# BEP31_final.net
KiCad netlist of a schematic drawn in EAGLE
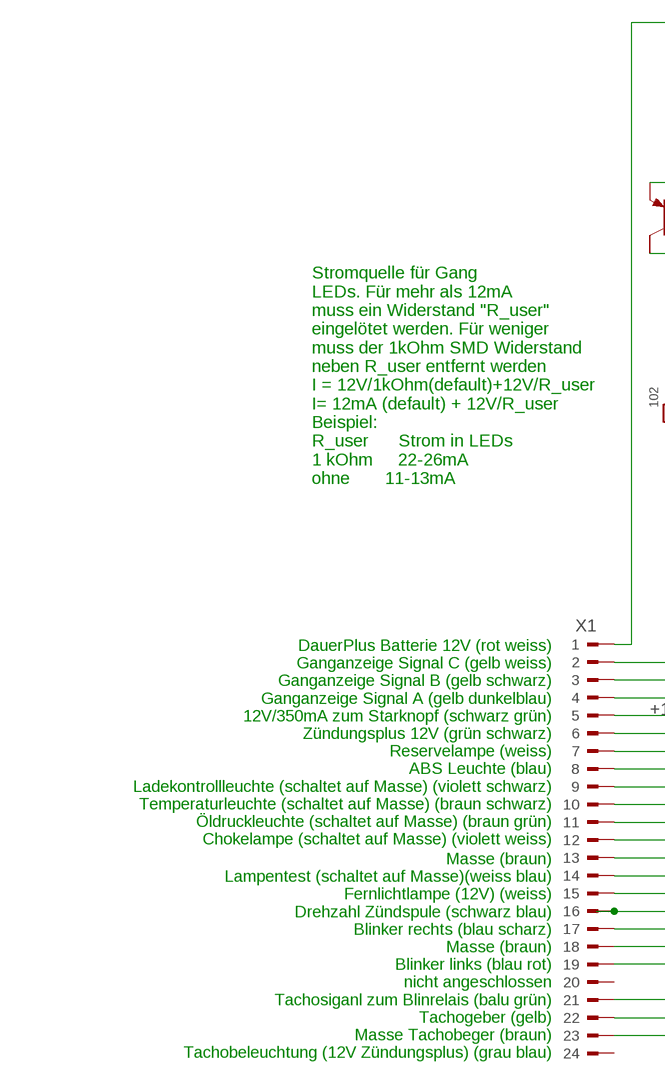
[diagram p0: schematic, sheet 1, part 1 of 2]
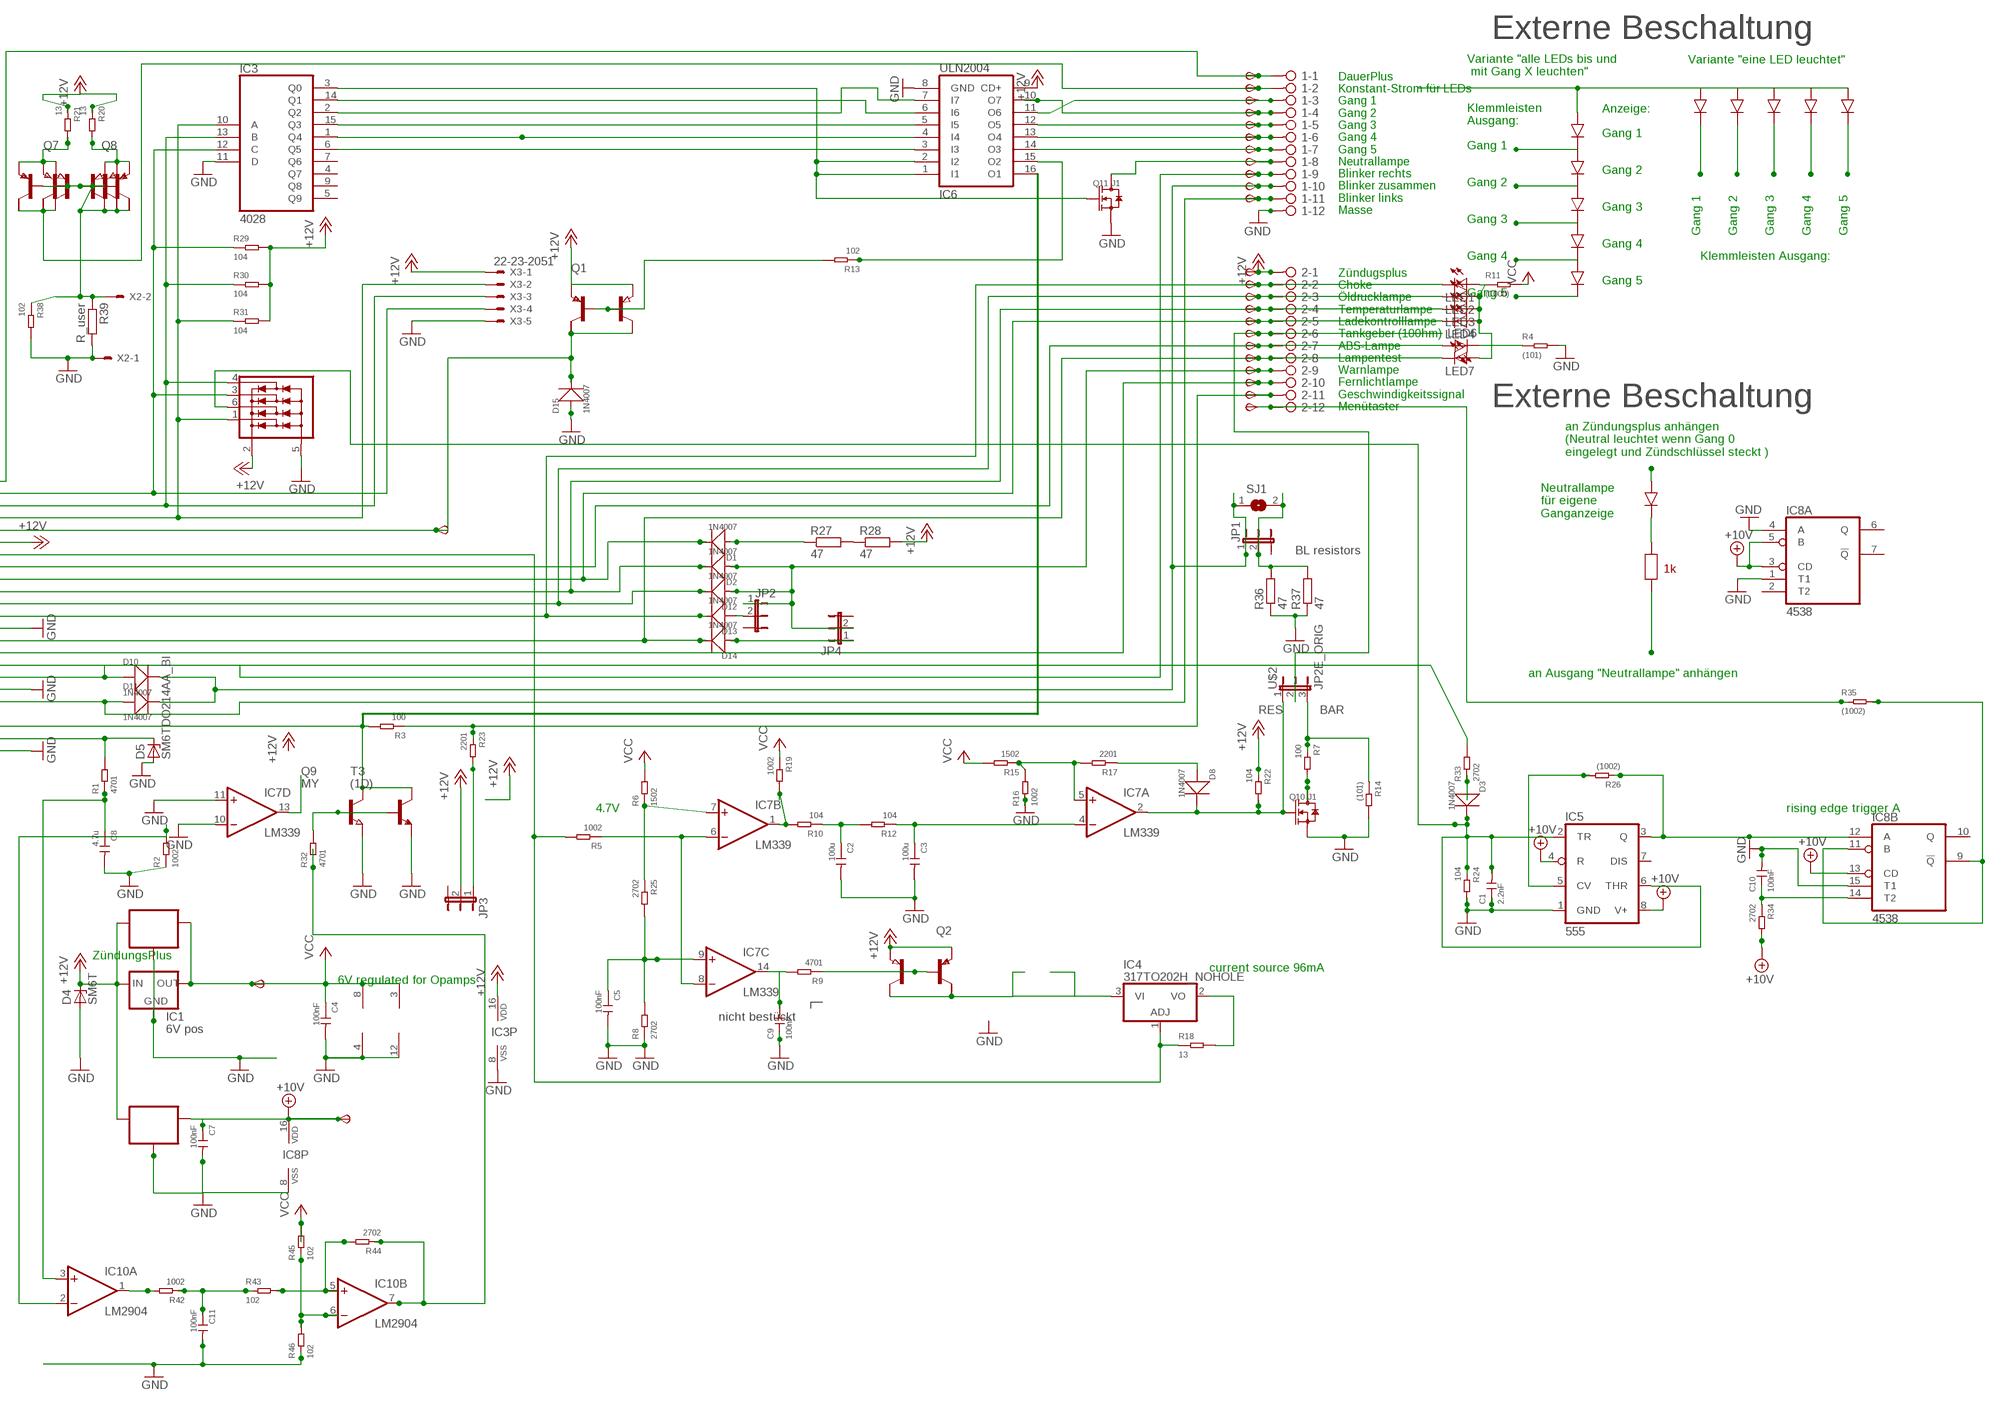
[diagram p1: schematic, sheet 1, part 2 of 2]

(export (version "E")
  (design (tool "Eeschema 10.0.6"))
  (components
    (comp (ref "1")
      (value "2081-1132")
      (footprint "eagle-import:12-PIN")
      (libsource (lib "eagle-import") (part "2081-1132"))
    )
    (comp (ref "2")
      (value "2081-1132")
      (footprint "eagle-import:12-PIN")
      (libsource (lib "eagle-import") (part "2081-1132"))
    )
    (comp (ref "6V")
      (value "TPSB2.0")
      (footprint "eagle-import:B2.0")
      (libsource (lib "eagle-import") (part "TPSB2.0"))
    )
    (comp (ref "10V")
      (value "TPSB2.0")
      (footprint "eagle-import:B2.0")
      (libsource (lib "eagle-import") (part "TPSB2.0"))
    )
    (comp (ref "C1")
      (value "2.2nF")
      (footprint "eagle-import:C0805")
      (fields (field (name "MPN") "CC0805KRX7R9BB104"))
      (libsource (lib "eagle-import") (part "CERAMIC-100NF-50V-10%-X7R(0805)"))
    )
    (comp (ref "C2")
      (value "100u")
      (footprint "eagle-import:C1206")
      (fields (field (name "MPN") "GRM31CR60J107ME39L"))
      (libsource (lib "eagle-import") (part "CERAMIC-100UF-6.3V-20%-X5R(1206)"))
    )
    (comp (ref "C3")
      (value "100u")
      (footprint "eagle-import:C1206")
      (fields (field (name "MPN") "GRM31CR60J107ME39L"))
      (libsource (lib "eagle-import") (part "CERAMIC-100UF-6.3V-20%-X5R(1206)"))
    )
    (comp (ref "C4")
      (value "100nF")
      (footprint "eagle-import:C0805")
      (fields (field (name "MPN") "CC0805KRX7R9BB104"))
      (libsource (lib "eagle-import") (part "CERAMIC-100NF-50V-10%-X7R(0805)"))
    )
    (comp (ref "C5")
      (value "100nF")
      (footprint "eagle-import:C0805")
      (fields (field (name "MPN") "CC0805KRX7R9BB104"))
      (libsource (lib "eagle-import") (part "CERAMIC-100NF-50V-10%-X7R(0805)"))
    )
    (comp (ref "C7")
      (value "100nF")
      (footprint "eagle-import:C0805")
      (fields (field (name "MPN") "CC0805KRX7R9BB104"))
      (libsource (lib "eagle-import") (part "CERAMIC-100NF-50V-10%-X7R(0805)"))
    )
    (comp (ref "C8")
      (value "4.7u")
      (footprint "eagle-import:C0805")
      (fields (field (name "MPN") "CC0805KKX5R8BB475"))
      (libsource (lib "eagle-import") (part "CERAMIC-4.7UF-25V-10%-X5R(0805)"))
    )
    (comp (ref "C9")
      (value "100nF")
      (footprint "eagle-import:C0805")
      (fields (field (name "MPN") "CC0805KRX7R9BB104"))
      (libsource (lib "eagle-import") (part "CERAMIC-100NF-50V-10%-X7R(0805)"))
    )
    (comp (ref "C10")
      (value "100nF")
      (footprint "eagle-import:C0805")
      (fields (field (name "MPN") "CC0805KRX7R9BB104"))
      (libsource (lib "eagle-import") (part "CERAMIC-100NF-50V-10%-X7R(0805)"))
    )
    (comp (ref "C11")
      (value "100nF")
      (footprint "eagle-import:C0805")
      (fields (field (name "MPN") "CC0805KRX7R9BB104"))
      (libsource (lib "eagle-import") (part "CERAMIC-100NF-50V-10%-X7R(0805)"))
    )
    (comp (ref "D1")
      (value "1N4007")
      (footprint "eagle-import:DO-214AC")
      (libsource (lib "eagle-import") (part "DIODE-GEN-PURPOSE-1KV-1A(DO-214AC)"))
    )
    (comp (ref "D2")
      (value "1N4007")
      (footprint "eagle-import:DO-214AC-1206MOUNT")
      (libsource (lib "eagle-import") (part "DIODE-GEN-PURPOSE-1KV-1A(DO-214AC)DO-214AC/1206"))
    )
    (comp (ref "D3")
      (value "1N4007")
      (footprint "eagle-import:DO-214AC")
      (libsource (lib "eagle-import") (part "DIODE-GEN-PURPOSE-1KV-1A(DO-214AC)"))
    )
    (comp (ref "D4")
      (value "SM6T")
      (footprint "eagle-import:DO214AA")
      (libsource (lib "eagle-import") (part "SM6T"))
    )
    (comp (ref "D5")
      (value "SM6TDO214AA_BI")
      (footprint "eagle-import:DO214AA_BI")
      (libsource (lib "eagle-import") (part "SM6TDO214AA_BI"))
    )
    (comp (ref "D8")
      (value "1N4007")
      (footprint "eagle-import:DO-214AC")
      (libsource (lib "eagle-import") (part "DIODE-GEN-PURPOSE-1KV-1A(DO-214AC)"))
    )
    (comp (ref "D10")
      (value "1N4007")
      (footprint "eagle-import:DO-214AC")
      (libsource (lib "eagle-import") (part "DIODE-GEN-PURPOSE-1KV-1A(DO-214AC)"))
    )
    (comp (ref "D11")
      (value "1N4007")
      (footprint "eagle-import:DO-214AC")
      (libsource (lib "eagle-import") (part "DIODE-GEN-PURPOSE-1KV-1A(DO-214AC)"))
    )
    (comp (ref "D12")
      (value "1N4007")
      (footprint "eagle-import:DO-214AC-1206MOUNT")
      (libsource (lib "eagle-import") (part "DIODE-GEN-PURPOSE-1KV-1A(DO-214AC)DO-214AC/1206"))
    )
    (comp (ref "D13")
      (value "1N4007")
      (footprint "eagle-import:DO-214AC-1206MOUNT")
      (libsource (lib "eagle-import") (part "DIODE-GEN-PURPOSE-1KV-1A(DO-214AC)DO-214AC/1206"))
    )
    (comp (ref "D14")
      (value "1N4007")
      (footprint "eagle-import:DO-214AC-1206MOUNT")
      (libsource (lib "eagle-import") (part "DIODE-GEN-PURPOSE-1KV-1A(DO-214AC)DO-214AC/1206"))
    )
    (comp (ref "D15")
      (value "1N4007")
      (footprint "eagle-import:DO-214AC")
      (libsource (lib "eagle-import") (part "DIODE-GEN-PURPOSE-1KV-1A(DO-214AC)"))
    )
    (comp (ref "IC1")
      (value "6V pos")
      (footprint "eagle-import:78LXX")
      (libsource (lib "eagle-import") (part "v-reg_78LXX"))
    )
    (comp (ref "IC2")
      (value "78LXXSOT89_ROUND")
      (footprint "eagle-import:SOT89_ROUND")
      (libsource (lib "eagle-import") (part "78LXXSOT89_ROUND"))
    )
    (comp (ref "IC3")
      (value "4028")
      (footprint "eagle-import:SO16")
      (libsource (lib "eagle-import") (part "4028D"))
    )
    (comp (ref "IC4")
      (value "317TO202H_NOHOLE")
      (footprint "eagle-import:TO220H_NOHOLE")
      (libsource (lib "eagle-import") (part "317TO202H_NOHOLE"))
    )
    (comp (ref "IC5")
      (value "555")
      (footprint "eagle-import:SO08")
      (libsource (lib "eagle-import") (part "555DNE"))
    )
    (comp (ref "IC6")
      (value "ULN2004")
      (footprint "eagle-import:SO16")
      (libsource (lib "eagle-import") (part "ULN2004AD"))
    )
    (comp (ref "IC7")
      (value "LM339")
      (footprint "eagle-import:SO14")
      (libsource (lib "eagle-import") (part "LM339D"))
    )
    (comp (ref "IC8")
      (value "4538")
      (footprint "eagle-import:SO16")
      (libsource (lib "eagle-import") (part "4538D"))
    )
    (comp (ref "IC9")
      (value "78LXXSOT89_ROUND")
      (footprint "eagle-import:SOT89_ROUND")
      (libsource (lib "eagle-import") (part "78LXXSOT89_ROUND"))
    )
    (comp (ref "IC10")
      (value "LM2904")
      (footprint "eagle-import:SO08")
      (libsource (lib "eagle-import") (part "LM358D"))
    )
    (comp (ref "JP1")
      (value "JP2EJP2_SMALLPADS")
      (footprint "eagle-import:JP2_SMALLPADS")
      (libsource (lib "eagle-import") (part "JP2EJP2_SMALLPADS"))
    )
    (comp (ref "JP2")
      (value "JP2EJP2_SMALLPADS")
      (footprint "eagle-import:JP2_SMALLPADS")
      (libsource (lib "eagle-import") (part "JP2EJP2_SMALLPADS"))
    )
    (comp (ref "JP3")
      (value "JP2EJP2_SMALLPADS")
      (footprint "eagle-import:JP2_SMALLPADS")
      (libsource (lib "eagle-import") (part "JP2EJP2_SMALLPADS"))
    )
    (comp (ref "JP4")
      (value "JP2EJP2_SMALLPADS")
      (footprint "eagle-import:JP2_SMALLPADS")
      (libsource (lib "eagle-import") (part "JP2EJP2_SMALLPADS"))
    )
    (comp (ref "LED1")
      (value "LEDLD260")
      (footprint "eagle-import:LD260")
      (libsource (lib "eagle-import") (part "LEDLD260"))
    )
    (comp (ref "LED2")
      (value "LEDLD260")
      (footprint "eagle-import:LD260")
      (libsource (lib "eagle-import") (part "LEDLD260"))
    )
    (comp (ref "LED3")
      (value "LEDLD260")
      (footprint "eagle-import:LD260")
      (libsource (lib "eagle-import") (part "LEDLD260"))
    )
    (comp (ref "LED4")
      (value "LEDLD260")
      (footprint "eagle-import:LD260")
      (libsource (lib "eagle-import") (part "LEDLD260"))
    )
    (comp (ref "LED6")
      (value "LEDLD260")
      (footprint "eagle-import:LD260")
      (libsource (lib "eagle-import") (part "LEDLD260"))
    )
    (comp (ref "LED7")
      (value "LEDLD260")
      (footprint "eagle-import:LD260")
      (libsource (lib "eagle-import") (part "LEDLD260"))
    )
    (comp (ref "Q1")
      (value "PNP-TRANSISTOR_SOT89")
      (footprint "eagle-import:SOT89")
      (libsource (lib "eagle-import") (part "PNP-TRANSISTOR_SOT89"))
    )
    (comp (ref "Q2")
      (value "PNP-TRANSISTOR_SOT89")
      (footprint "eagle-import:SOT89")
      (libsource (lib "eagle-import") (part "PNP-TRANSISTOR_SOT89"))
    )
    (comp (ref "Q3")
      (value "AH-16")
      (footprint "eagle-import:SOT223")
      (libsource (lib "eagle-import") (part "BCP53T1"))
    )
    (comp (ref "Q4")
      (value "(AH-16)")
      (footprint "eagle-import:SOT223")
      (libsource (lib "eagle-import") (part "BCP53T1"))
    )
    (comp (ref "Q5")
      (value "(AH-16)")
      (footprint "eagle-import:SOT223")
      (libsource (lib "eagle-import") (part "BCP53T1"))
    )
    (comp (ref "Q6")
      (value "(AH-16)")
      (footprint "eagle-import:SOT223")
      (libsource (lib "eagle-import") (part "BCP53T1"))
    )
    (comp (ref "Q7")
      (value "PNP-TRANSISTOR_SOT89")
      (footprint "eagle-import:SOT89")
      (libsource (lib "eagle-import") (part "PNP-TRANSISTOR_SOT89"))
    )
    (comp (ref "Q8")
      (value "PNP-TRANSISTOR_SOT89")
      (footprint "eagle-import:SOT89")
      (libsource (lib "eagle-import") (part "PNP-TRANSISTOR_SOT89"))
    )
    (comp (ref "Q9")
      (value "MY")
      (footprint "eagle-import:SOT89")
      (libsource (lib "eagle-import") (part "NPN-TRANSISTOR_SOT89"))
    )
    (comp (ref "Q10")
      (value "J1")
      (footprint "eagle-import:SOT-23")
      (fields (field (name "MPN") "BSS138W-7-F"))
      (libsource (lib "eagle-import") (part "SMD-MOSFET-N-CH-50V-200MA-BSS138W-7-F(SOT-23)"))
    )
    (comp (ref "Q11")
      (value "J1")
      (footprint "eagle-import:SOT-23")
      (fields (field (name "MPN") "BSS138W-7-F"))
      (libsource (lib "eagle-import") (part "SMD-MOSFET-N-CH-50V-200MA-BSS138W-7-F(SOT-23)"))
    )
    (comp (ref "R1")
      (value "4701")
      (footprint "eagle-import:R0805")
      (fields (field (name "MPN") "RC0805JR-074K7L"))
      (libsource (lib "eagle-import") (part "SMD-RES-4.7K-5%-1/8W(0805)"))
    )
    (comp (ref "R2")
      (value "1002")
      (footprint "eagle-import:R0805")
      (fields (field (name "MPN") "RC0805FR-0710KL"))
      (libsource (lib "eagle-import") (part "SMD-RES-10K-1%-1/8W(0805)"))
    )
    (comp (ref "R3")
      (value "100")
      (footprint "eagle-import:R0805")
      (fields (field (name "MPN") "RC0805JR-07220RL"))
      (libsource (lib "eagle-import") (part "SMD-RES-220R-5%-1/8W(0805)"))
    )
    (comp (ref "R4")
      (value "(101)")
      (footprint "eagle-import:R0805")
      (fields (field (name "MPN") "RC0805JR-07100RL"))
      (libsource (lib "eagle-import") (part "SMD-RES-100R-5%-1/8W(0805)"))
    )
    (comp (ref "R5")
      (value "1002")
      (footprint "eagle-import:R0805")
      (fields (field (name "MPN") "RC0805FR-0710KL"))
      (libsource (lib "eagle-import") (part "SMD-RES-10K-1%-1/8W(0805)"))
    )
    (comp (ref "R6")
      (value "1502")
      (footprint "eagle-import:R0805")
      (fields (field (name "MPN") "RC0805FR-0710KL"))
      (libsource (lib "eagle-import") (part "SMD-RES-10K-1%-1/8W(0805)"))
    )
    (comp (ref "R7")
      (value "100")
      (footprint "eagle-import:R0805")
      (fields (field (name "MPN") "RC0805JR-072K2L"))
      (libsource (lib "eagle-import") (part "SMD-RES-2.2K-5%-1/8W(0805)"))
    )
    (comp (ref "R8")
      (value "2702")
      (footprint "eagle-import:R0805")
      (fields (field (name "MPN") "RC0805JR-074K7L"))
      (libsource (lib "eagle-import") (part "SMD-RES-4.7K-5%-1/8W(0805)"))
    )
    (comp (ref "R9")
      (value "4701")
      (footprint "eagle-import:R0805")
      (fields (field (name "MPN") "RC0805JR-074K7L"))
      (libsource (lib "eagle-import") (part "SMD-RES-4.7K-5%-1/8W(0805)"))
    )
    (comp (ref "R10")
      (value "104")
      (footprint "eagle-import:R0805")
      (fields (field (name "MPN") "RC0805FR-0710KL"))
      (libsource (lib "eagle-import") (part "SMD-RES-10K-1%-1/8W(0805)"))
    )
    (comp (ref "R11")
      (value "(1000)")
      (footprint "eagle-import:R0805")
      (fields (field (name "MPN") "RC0805JR-07100RL"))
      (libsource (lib "eagle-import") (part "SMD-RES-100R-5%-1/8W(0805)"))
    )
    (comp (ref "R12")
      (value "104")
      (footprint "eagle-import:R0805")
      (fields (field (name "MPN") "RC0805FR-0710KL"))
      (libsource (lib "eagle-import") (part "SMD-RES-10K-1%-1/8W(0805)"))
    )
    (comp (ref "R13")
      (value "102")
      (footprint "eagle-import:R0805")
      (fields (field (name "MPN") "RC0805JR-071KL"))
      (libsource (lib "eagle-import") (part "SMD-RES-1K-5%-1/8W(0805)"))
    )
    (comp (ref "R14")
      (value "(101)")
      (footprint "eagle-import:R0805")
      (fields (field (name "MPN") "RC0805JR-072K2L"))
      (libsource (lib "eagle-import") (part "SMD-RES-2.2K-5%-1/8W(0805)"))
    )
    (comp (ref "R15")
      (value "1502")
      (footprint "eagle-import:R0805")
      (fields (field (name "MPN") "RC0805FR-0710KL"))
      (libsource (lib "eagle-import") (part "SMD-RES-10K-1%-1/8W(0805)"))
    )
    (comp (ref "R16")
      (value "1002")
      (footprint "eagle-import:R0805")
      (fields (field (name "MPN") "RC0805FR-0710KL"))
      (libsource (lib "eagle-import") (part "SMD-RES-10K-1%-1/8W(0805)"))
    )
    (comp (ref "R17")
      (value "2201")
      (footprint "eagle-import:R0805")
      (fields (field (name "MPN") "RC0805JR-072K2L"))
      (libsource (lib "eagle-import") (part "SMD-RES-2.2K-5%-1/8W(0805)"))
    )
    (comp (ref "R18")
      (value "13")
      (footprint "eagle-import:R1206")
      (fields (field (name "MPN") "RC1206JR-0713RL"))
      (libsource (lib "eagle-import") (part "SMD-RES-13R-5%-1/4W(1206)"))
    )
    (comp (ref "R19")
      (value "1002")
      (footprint "eagle-import:R0805")
      (fields (field (name "MPN") "RC0805FR-0710KL"))
      (libsource (lib "eagle-import") (part "SMD-RES-10K-1%-1/8W(0805)"))
    )
    (comp (ref "R20")
      (value "13")
      (footprint "eagle-import:R1206")
      (fields (field (name "MPN") "RC1206JR-0713RL"))
      (libsource (lib "eagle-import") (part "SMD-RES-13R-5%-1/4W(1206)"))
    )
    (comp (ref "R21")
      (value "13")
      (footprint "eagle-import:R1206")
      (fields (field (name "MPN") "RC1206JR-0713RL"))
      (libsource (lib "eagle-import") (part "SMD-RES-13R-5%-1/4W(1206)"))
    )
    (comp (ref "R22")
      (value "104")
      (footprint "eagle-import:R0805")
      (fields (field (name "MPN") "RC0805FR-0710KL"))
      (libsource (lib "eagle-import") (part "SMD-RES-10K-1%-1/8W(0805)"))
    )
    (comp (ref "R23")
      (value "2201")
      (footprint "eagle-import:R0805")
      (fields (field (name "MPN") "RC0805JR-072K2L"))
      (libsource (lib "eagle-import") (part "SMD-RES-2.2K-5%-1/8W(0805)"))
    )
    (comp (ref "R24")
      (value "104")
      (footprint "eagle-import:R0805")
      (fields (field (name "MPN") "RC0805FR-0710KL"))
      (libsource (lib "eagle-import") (part "SMD-RES-10K-1%-1/8W(0805)"))
    )
    (comp (ref "R25")
      (value "2702")
      (footprint "eagle-import:R0805")
      (fields (field (name "MPN") "RC0805JR-074K7L"))
      (libsource (lib "eagle-import") (part "SMD-RES-4.7K-5%-1/8W(0805)"))
    )
    (comp (ref "R26")
      (value "(1002)")
      (footprint "eagle-import:R0805")
      (fields (field (name "MPN") "RC0805FR-0710KL"))
      (libsource (lib "eagle-import") (part "SMD-RES-10K-1%-1/8W(0805)"))
    )
    (comp (ref "R27")
      (value "47")
      (footprint "eagle-import:V235_17_1MM")
      (libsource (lib "eagle-import") (part "R-EU_V235/17_1MM"))
    )
    (comp (ref "R28")
      (value "47")
      (footprint "eagle-import:V235_17_1MM")
      (libsource (lib "eagle-import") (part "R-EU_V235/17_1MM"))
    )
    (comp (ref "R29")
      (value "104")
      (footprint "eagle-import:R0805")
      (fields (field (name "MPN") "RC0805FR-0710KL"))
      (libsource (lib "eagle-import") (part "SMD-RES-10K-1%-1/8W(0805)"))
    )
    (comp (ref "R30")
      (value "104")
      (footprint "eagle-import:R0805")
      (fields (field (name "MPN") "RC0805FR-0710KL"))
      (libsource (lib "eagle-import") (part "SMD-RES-10K-1%-1/8W(0805)"))
    )
    (comp (ref "R31")
      (value "104")
      (footprint "eagle-import:R0805")
      (fields (field (name "MPN") "RC0805FR-0710KL"))
      (libsource (lib "eagle-import") (part "SMD-RES-10K-1%-1/8W(0805)"))
    )
    (comp (ref "R32")
      (value "4701")
      (footprint "eagle-import:R0805")
      (fields (field (name "MPN") "RC0805JR-074K7L"))
      (libsource (lib "eagle-import") (part "SMD-RES-4.7K-5%-1/8W(0805)"))
    )
    (comp (ref "R33")
      (value "2702")
      (footprint "eagle-import:R0805")
      (fields (field (name "MPN") "RC0805FR-0710KL"))
      (libsource (lib "eagle-import") (part "SMD-RES-10K-1%-1/8W(0805)"))
    )
    (comp (ref "R34")
      (value "2702")
      (footprint "eagle-import:R0805")
      (fields (field (name "MPN") "RC0805JR-074K7L"))
      (libsource (lib "eagle-import") (part "SMD-RES-4.7K-5%-1/8W(0805)"))
    )
    (comp (ref "R35")
      (value "(1002)")
      (footprint "eagle-import:R0805")
      (fields (field (name "MPN") "RC0805JR-074K7L"))
      (libsource (lib "eagle-import") (part "SMD-RES-4.7K-5%-1/8W(0805)"))
    )
    (comp (ref "R36")
      (value "47")
      (footprint "eagle-import:V235_17_1MM")
      (libsource (lib "eagle-import") (part "R-EU_V235/17_1MM"))
    )
    (comp (ref "R37")
      (value "47")
      (footprint "eagle-import:V235_17_1MM")
      (libsource (lib "eagle-import") (part "R-EU_V235/17_1MM"))
    )
    (comp (ref "R38")
      (value "102")
      (footprint "eagle-import:R0805")
      (fields (field (name "MPN") "RC0805JR-071KL"))
      (libsource (lib "eagle-import") (part "SMD-RES-1K-5%-1/8W(0805)"))
    )
    (comp (ref "R39")
      (value "R_user")
      (footprint "eagle-import:R0805")
      (libsource (lib "eagle-import") (part "R-EU_R0805"))
    )
    (comp (ref "R42")
      (value "1002")
      (footprint "eagle-import:R0805")
      (fields (field (name "MPN") "RC0805FR-0710KL"))
      (libsource (lib "eagle-import") (part "SMD-RES-10K-1%-1/8W(0805)"))
    )
    (comp (ref "R43")
      (value "102")
      (footprint "eagle-import:R0805")
      (fields (field (name "MPN") "RC0805JR-071KL"))
      (libsource (lib "eagle-import") (part "SMD-RES-1K-5%-1/8W(0805)"))
    )
    (comp (ref "R44")
      (value "2702")
      (footprint "eagle-import:R0805")
      (fields (field (name "MPN") "RC0805JR-074K7L"))
      (libsource (lib "eagle-import") (part "SMD-RES-4.7K-5%-1/8W(0805)"))
    )
    (comp (ref "R45")
      (value "102")
      (footprint "eagle-import:R0805")
      (fields (field (name "MPN") "RC0805JR-071KL"))
      (libsource (lib "eagle-import") (part "SMD-RES-1K-5%-1/8W(0805)"))
    )
    (comp (ref "R46")
      (value "102")
      (footprint "eagle-import:R0805")
      (fields (field (name "MPN") "RC0805JR-071KL"))
      (libsource (lib "eagle-import") (part "SMD-RES-1K-5%-1/8W(0805)"))
    )
    (comp (ref "SJ1") (value "SJ") (footprint "eagle-import:SJ") (libsource (lib "eagle-import") (part "SJ")))
    (comp (ref "START")
      (value "TPSB2.0")
      (footprint "eagle-import:B2.0")
      (libsource (lib "eagle-import") (part "TPSB2.0"))
    )
    (comp (ref "T1")
      (value "PNP2SM8")
      (footprint "eagle-import:SM8")
      (libsource (lib "eagle-import") (part "PNP2SM8"))
    )
    (comp (ref "T3")
      (value "(1D)")
      (footprint "eagle-import:SOT23-BEC")
      (libsource (lib "eagle-import") (part "-NPN-SOT23-BECMMBTA42LT1"))
    )
    (comp (ref "TP1")
      (value "TPSB2.0")
      (footprint "eagle-import:B2.0")
      (libsource (lib "eagle-import") (part "TPSB2.0"))
    )
    (comp (ref "TP2")
      (value "TPSB2.0")
      (footprint "eagle-import:B2.0")
      (libsource (lib "eagle-import") (part "TPSB2.0"))
    )
    (comp (ref "TP3")
      (value "TPSB2.0")
      (footprint "eagle-import:B2.0")
      (libsource (lib "eagle-import") (part "TPSB2.0"))
    )
    (comp (ref "TP4")
      (value "TPSB2.0")
      (footprint "eagle-import:B2.0")
      (libsource (lib "eagle-import") (part "TPSB2.0"))
    )
    (comp (ref "TP5")
      (value "TPSB2.0")
      (footprint "eagle-import:B2.0")
      (libsource (lib "eagle-import") (part "TPSB2.0"))
    )
    (comp (ref "TP6")
      (value "TPSB2.0")
      (footprint "eagle-import:B2.0")
      (libsource (lib "eagle-import") (part "TPSB2.0"))
    )
    (comp (ref "TP7")
      (value "TPSB2.0")
      (footprint "eagle-import:B2.0")
      (libsource (lib "eagle-import") (part "TPSB2.0"))
    )
    (comp (ref "TP8")
      (value "TPSB2.0")
      (footprint "eagle-import:B2.0")
      (libsource (lib "eagle-import") (part "TPSB2.0"))
    )
    (comp (ref "TP9")
      (value "TPSB2.0")
      (footprint "eagle-import:B2.0")
      (libsource (lib "eagle-import") (part "TPSB2.0"))
    )
    (comp (ref "TP10")
      (value "TPSB2.0")
      (footprint "eagle-import:B2.0")
      (libsource (lib "eagle-import") (part "TPSB2.0"))
    )
    (comp (ref "TP11")
      (value "TPSB2.0")
      (footprint "eagle-import:B2.0")
      (libsource (lib "eagle-import") (part "TPSB2.0"))
    )
    (comp (ref "TP12")
      (value "TPSB2.0")
      (footprint "eagle-import:B2.0")
      (libsource (lib "eagle-import") (part "TPSB2.0"))
    )
    (comp (ref "TP13")
      (value "TPSB2.0")
      (footprint "eagle-import:B2.0")
      (libsource (lib "eagle-import") (part "TPSB2.0"))
    )
    (comp (ref "TP16")
      (value "TPSB2.0")
      (footprint "eagle-import:B2.0")
      (libsource (lib "eagle-import") (part "TPSB2.0"))
    )
    (comp (ref "TP17")
      (value "TPSB2.0")
      (footprint "eagle-import:B2.0")
      (libsource (lib "eagle-import") (part "TPSB2.0"))
    )
    (comp (ref "TP18")
      (value "TPSB2.0")
      (footprint "eagle-import:B2.0")
      (libsource (lib "eagle-import") (part "TPSB2.0"))
    )
    (comp (ref "TP19")
      (value "TPSB2.0")
      (footprint "eagle-import:B2.0")
      (libsource (lib "eagle-import") (part "TPSB2.0"))
    )
    (comp (ref "TP21")
      (value "TPSB2.0")
      (footprint "eagle-import:B2.0")
      (libsource (lib "eagle-import") (part "TPSB2.0"))
    )
    (comp (ref "TP22")
      (value "TPSB2.0")
      (footprint "eagle-import:B2.0")
      (libsource (lib "eagle-import") (part "TPSB2.0"))
    )
    (comp (ref "TP23")
      (value "TPSB2.0")
      (footprint "eagle-import:B2.0")
      (libsource (lib "eagle-import") (part "TPSB2.0"))
    )
    (comp (ref "TP24")
      (value "TPSB1,27")
      (footprint "eagle-import:B1,27")
      (libsource (lib "eagle-import") (part "TPSB1,27"))
    )
    (comp (ref "TP25")
      (value "TPSB2.0")
      (footprint "eagle-import:B2.0")
      (libsource (lib "eagle-import") (part "TPSB2.0"))
    )
    (comp (ref "TP26")
      (value "TPSB2.0")
      (footprint "eagle-import:B2.0")
      (libsource (lib "eagle-import") (part "TPSB2.0"))
    )
    (comp (ref "U$2")
      (value "JP2E_ORIG")
      (footprint "eagle-import:JP2_ORIG_SMALLPADS")
      (libsource (lib "eagle-import") (part "JP2E_ORIG"))
    )
    (comp (ref "U$3")
      (value "NUP4304SOT457_R")
      (footprint "eagle-import:SOT457R_PHILIPS")
      (libsource (lib "eagle-import") (part "NUP4304SOT457_R"))
    )
    (comp (ref "X1")
      (value "CON_BMWV2")
      (footprint "eagle-import:24-PIN_V2")
      (libsource (lib "eagle-import") (part "CON_BMWV2"))
    )
    (comp (ref "X2")
      (value "22-23-2021")
      (footprint "eagle-import:22-23-2021")
      (fields (field (name "MF") "MOLEX"))
      (libsource (lib "eagle-import") (part "22-23-2021"))
    )
    (comp (ref "X3")
      (value "22-23-2051")
      (footprint "eagle-import:22-23-2051")
      (fields (field (name "MF") "MOLEX"))
      (libsource (lib "eagle-import") (part "22-23-2051"))
    )
  )
  (nets
    (net (code "1") (name "+10V") (class "Default")
      (node (ref "10V") (pin "TP") (pinfunction "PP_TP") (pintype "input"))
      (node (ref "C7") (pin "1") (pinfunction "1_1") (pintype "passive"))
      (node (ref "IC5") (pin "4") (pinfunction "R_4") (pintype "input"))
      (node (ref "IC5") (pin "8") (pinfunction "V+_8") (pintype "power_in"))
      (node (ref "IC8") (pin "13") (pinfunction "CD_13") (pintype "input"))
      (node (ref "IC8") (pin "16") (pinfunction "VDD_16") (pintype "power_in"))
      (node (ref "IC8") (pin "3") (pinfunction "CD_3") (pintype "input"))
      (node (ref "IC8") (pin "5") (pinfunction "B_5") (pintype "input"))
      (node (ref "IC9") (pin "1") (pinfunction "OUT_1") (pintype "passive"))
      (node (ref "R34") (pin "2") (pinfunction "2_2") (pintype "passive"))
    )
    (net (code "2") (name "+12V") (class "Default")
      (node (ref "2") (pin "1") (pinfunction "KL_1") (pintype "passive"))
      (node (ref "D4") (pin "C") (pinfunction "C_C") (pintype "passive"))
      (node (ref "IC1") (pin "IN") (pinfunction "IN_IN") (pintype "input"))
      (node (ref "IC2") (pin "3") (pinfunction "IN_3") (pintype "input"))
      (node (ref "IC3") (pin "16") (pinfunction "VDD_16") (pintype "power_in"))
      (node (ref "IC6") (pin "9") (pinfunction "CD+_9") (pintype "passive"))
      (node (ref "IC9") (pin "3") (pinfunction "IN_3") (pintype "input"))
      (node (ref "JP3") (pin "2") (pinfunction "2_2") (pintype "passive"))
      (node (ref "Q1") (pin "3") (pinfunction "E_3") (pintype "passive"))
      (node (ref "Q2") (pin "3") (pinfunction "E_3") (pintype "passive"))
      (node (ref "Q3") (pin "3") (pinfunction "E_3") (pintype "passive"))
      (node (ref "Q4") (pin "3") (pinfunction "E_3") (pintype "passive"))
      (node (ref "R20") (pin "1") (pinfunction "1_1") (pintype "passive"))
      (node (ref "R21") (pin "1") (pinfunction "1_1") (pintype "passive"))
      (node (ref "R22") (pin "1") (pinfunction "1_1") (pintype "passive"))
      (node (ref "R28") (pin "2") (pinfunction "2_2") (pintype "passive"))
      (node (ref "R29") (pin "2") (pinfunction "2_2") (pintype "passive"))
      (node (ref "R30") (pin "2") (pinfunction "2_2") (pintype "passive"))
      (node (ref "R31") (pin "2") (pinfunction "2_2") (pintype "passive"))
      (node (ref "TP12") (pin "TP") (pinfunction "PP_TP") (pintype "input"))
      (node (ref "U$3") (pin "2") (pinfunction "V+_2") (pintype "passive"))
      (node (ref "X1") (pin "6") (pinfunction "6_6") (pintype "passive"))
      (node (ref "X3") (pin "1") (pinfunction "S_1") (pintype "passive"))
    )
    (net (code "3") (name "GND") (class "Default")
      (node (ref "1") (pin "12") (pinfunction "KL_12") (pintype "passive"))
      (node (ref "C1") (pin "1") (pinfunction "1_1") (pintype "passive"))
      (node (ref "C10") (pin "2") (pinfunction "2_2") (pintype "passive"))
      (node (ref "C11") (pin "2") (pinfunction "2_2") (pintype "passive"))
      (node (ref "C2") (pin "2") (pinfunction "2_2") (pintype "passive"))
      (node (ref "C3") (pin "2") (pinfunction "2_2") (pintype "passive"))
      (node (ref "C4") (pin "2") (pinfunction "2_2") (pintype "passive"))
      (node (ref "C5") (pin "2") (pinfunction "2_2") (pintype "passive"))
      (node (ref "C7") (pin "2") (pinfunction "2_2") (pintype "passive"))
      (node (ref "C8") (pin "2") (pinfunction "2_2") (pintype "passive"))
      (node (ref "C9") (pin "1") (pinfunction "1_1") (pintype "passive"))
      (node (ref "D15") (pin "1") (pinfunction "+_1") (pintype "passive"))
      (node (ref "D4") (pin "A") (pinfunction "A_A") (pintype "passive"))
      (node (ref "D5") (pin "A") (pinfunction "A_A") (pintype "passive"))
      (node (ref "IC1") (pin "GND") (pinfunction "GND_GND") (pintype "input"))
      (node (ref "IC10") (pin "4") (pinfunction "V-_4") (pintype "power_in"))
      (node (ref "IC2") (pin "2") (pinfunction "GND_2") (pintype "input"))
      (node (ref "IC2") (pin "2@1") (pinfunction "GND_2@1") (pintype "input"))
      (node (ref "IC3") (pin "11") (pinfunction "D_11") (pintype "input"))
      (node (ref "IC3") (pin "8") (pinfunction "VSS_8") (pintype "power_in"))
      (node (ref "IC5") (pin "1") (pinfunction "GND_1") (pintype "power_in"))
      (node (ref "IC6") (pin "8") (pinfunction "GND_8") (pintype "power_in"))
      (node (ref "IC7") (pin "10") (pinfunction "-IN_10") (pintype "input"))
      (node (ref "IC7") (pin "11") (pinfunction "+IN_11") (pintype "input"))
      (node (ref "IC7") (pin "12") (pinfunction "GND_12") (pintype "power_in"))
      (node (ref "IC8") (pin "1") (pinfunction "T1_1") (pintype "input"))
      (node (ref "IC8") (pin "15") (pinfunction "T1_15") (pintype "input"))
      (node (ref "IC8") (pin "4") (pinfunction "A_4") (pintype "input"))
      (node (ref "IC8") (pin "8") (pinfunction "VSS_8") (pintype "power_in"))
      (node (ref "IC9") (pin "2") (pinfunction "GND_2") (pintype "input"))
      (node (ref "IC9") (pin "2@1") (pinfunction "GND_2@1") (pintype "input"))
      (node (ref "Q10") (pin "2") (pinfunction "S_2") (pintype "passive"))
      (node (ref "Q11") (pin "2") (pinfunction "S_2") (pintype "passive"))
      (node (ref "Q9") (pin "3") (pinfunction "E_3") (pintype "passive"))
      (node (ref "R14") (pin "2") (pinfunction "2_2") (pintype "passive"))
      (node (ref "R16") (pin "1") (pinfunction "1_1") (pintype "passive"))
      (node (ref "R2") (pin "1") (pinfunction "1_1") (pintype "passive"))
      (node (ref "R24") (pin "2") (pinfunction "2_2") (pintype "passive"))
      (node (ref "R36") (pin "1") (pinfunction "1_1") (pintype "passive"))
      (node (ref "R37") (pin "1") (pinfunction "1_1") (pintype "passive"))
      (node (ref "R38") (pin "2") (pinfunction "2_2") (pintype "passive"))
      (node (ref "R39") (pin "2") (pinfunction "2_2") (pintype "passive"))
      (node (ref "R4") (pin "2") (pinfunction "2_2") (pintype "passive"))
      (node (ref "R46") (pin "1") (pinfunction "1_1") (pintype "passive"))
      (node (ref "R8") (pin "1") (pinfunction "1_1") (pintype "passive"))
      (node (ref "T3") (pin "E") (pinfunction "E_E") (pintype "passive"))
      (node (ref "U$3") (pin "5") (pinfunction "V-_5") (pintype "passive"))
      (node (ref "X1") (pin "13") (pinfunction "13_13") (pintype "passive"))
      (node (ref "X1") (pin "18") (pinfunction "18_18") (pintype "passive"))
      (node (ref "X1") (pin "23") (pinfunction "23_23") (pintype "passive"))
      (node (ref "X2") (pin "1") (pinfunction "S_1") (pintype "passive"))
      (node (ref "X3") (pin "5") (pinfunction "S_5") (pintype "passive"))
    )
    (net (code "4") (name "Net-(1A-KL)") (class "Default")
      (node (ref "1") (pin "1") (pinfunction "KL_1") (pintype "passive"))
      (node (ref "TP1") (pin "TP") (pinfunction "PP_TP") (pintype "input"))
      (node (ref "X1") (pin "1") (pinfunction "1_1") (pintype "passive"))
    )
    (net (code "5") (name "Net-(1B-KL)") (class "Default")
      (node (ref "1") (pin "10") (pinfunction "KL_10") (pintype "passive"))
      (node (ref "D10") (pin "2") (pinfunction "-_2") (pintype "passive"))
      (node (ref "D11") (pin "2") (pinfunction "-_2") (pintype "passive"))
      (node (ref "JP1") (pin "1") (pinfunction "1_1") (pintype "passive"))
      (node (ref "SJ1") (pin "1") (pinfunction "1_1") (pintype "passive"))
      (node (ref "TP10") (pin "TP") (pinfunction "PP_TP") (pintype "input"))
    )
    (net (code "6") (name "Net-(1C-KL)") (class "Default")
      (node (ref "1") (pin "11") (pinfunction "KL_11") (pintype "passive"))
      (node (ref "D11") (pin "1") (pinfunction "+_1") (pintype "passive"))
      (node (ref "TP11") (pin "TP") (pinfunction "PP_TP") (pintype "input"))
      (node (ref "X1") (pin "19") (pinfunction "19_19") (pintype "passive"))
    )
    (net (code "7") (name "Net-(1E-KL)") (class "Default")
      (node (ref "1") (pin "2") (pinfunction "KL_2") (pintype "passive"))
      (node (ref "Q5") (pin "2") (pinfunction "C_2") (pintype "passive"))
      (node (ref "Q8") (pin "2") (pinfunction "C_2") (pintype "passive"))
      (node (ref "T1") (pin "8") (pinfunction "C1_8") (pintype "passive"))
      (node (ref "TP2") (pin "TP") (pinfunction "PP_TP") (pintype "input"))
    )
    (net (code "8") (name "Net-(1F-KL)") (class "Default")
      (node (ref "1") (pin "3") (pinfunction "KL_3") (pintype "passive"))
      (node (ref "IC6") (pin "11") (pinfunction "O6_11") (pintype "open_collector"))
      (node (ref "TP3") (pin "TP") (pinfunction "PP_TP") (pintype "input"))
    )
    (net (code "9") (name "Net-(1G-KL)") (class "Default")
      (node (ref "1") (pin "4") (pinfunction "KL_4") (pintype "passive"))
      (node (ref "IC6") (pin "10") (pinfunction "O7_10") (pintype "open_collector"))
      (node (ref "TP4") (pin "TP") (pinfunction "PP_TP") (pintype "input"))
    )
    (net (code "10") (name "Net-(1H-KL)") (class "Default")
      (node (ref "1") (pin "5") (pinfunction "KL_5") (pintype "passive"))
      (node (ref "IC6") (pin "12") (pinfunction "O5_12") (pintype "open_collector"))
      (node (ref "TP5") (pin "TP") (pinfunction "PP_TP") (pintype "input"))
    )
    (net (code "11") (name "Net-(1I-KL)") (class "Default")
      (node (ref "1") (pin "6") (pinfunction "KL_6") (pintype "passive"))
      (node (ref "IC6") (pin "13") (pinfunction "O4_13") (pintype "open_collector"))
      (node (ref "TP6") (pin "TP") (pinfunction "PP_TP") (pintype "input"))
    )
    (net (code "12") (name "Net-(1J-KL)") (class "Default")
      (node (ref "1") (pin "7") (pinfunction "KL_7") (pintype "passive"))
      (node (ref "IC6") (pin "14") (pinfunction "O3_14") (pintype "open_collector"))
      (node (ref "TP7") (pin "TP") (pinfunction "PP_TP") (pintype "input"))
    )
    (net (code "13") (name "Net-(1K-KL)") (class "Default")
      (node (ref "1") (pin "8") (pinfunction "KL_8") (pintype "passive"))
      (node (ref "Q11") (pin "3") (pinfunction "D_3") (pintype "passive"))
      (node (ref "TP8") (pin "TP") (pinfunction "PP_TP") (pintype "input"))
    )
    (net (code "14") (name "Net-(1L-KL)") (class "Default")
      (node (ref "1") (pin "9") (pinfunction "KL_9") (pintype "passive"))
      (node (ref "D10") (pin "1") (pinfunction "+_1") (pintype "passive"))
      (node (ref "TP9") (pin "TP") (pinfunction "PP_TP") (pintype "input"))
      (node (ref "X1") (pin "17") (pinfunction "17_17") (pintype "passive"))
    )
    (net (code "15") (name "Net-(2B-KL)") (class "Default")
      (node (ref "2") (pin "10") (pinfunction "KL_10") (pintype "passive"))
      (node (ref "TP25") (pin "TP") (pinfunction "PP_TP") (pintype "input"))
      (node (ref "X1") (pin "15") (pinfunction "15_15") (pintype "passive"))
    )
    (net (code "16") (name "Net-(2C-KL)") (class "Default")
      (node (ref "2") (pin "11") (pinfunction "KL_11") (pintype "passive"))
      (node (ref "R23") (pin "1") (pinfunction "1_1") (pintype "passive"))
      (node (ref "R3") (pin "1") (pinfunction "1_1") (pintype "passive"))
      (node (ref "TP26") (pin "TP") (pinfunction "PP_TP") (pintype "input"))
    )
    (net (code "17") (name "Net-(2D-KL)") (class "Default")
      (node (ref "2") (pin "12") (pinfunction "KL_12") (pintype "passive"))
      (node (ref "R35") (pin "1") (pinfunction "1_1") (pintype "passive"))
      (node (ref "TP13") (pin "TP") (pinfunction "PP_TP") (pintype "input"))
    )
    (net (code "18") (name "Net-(2E-KL)") (class "Default")
      (node (ref "2") (pin "2") (pinfunction "KL_2") (pintype "passive"))
      (node (ref "D13") (pin "2") (pinfunction "-_2") (pintype "passive"))
      (node (ref "LED1") (pin "K") (pinfunction "C_K") (pintype "passive"))
      (node (ref "TP16") (pin "TP") (pinfunction "PP_TP") (pintype "input"))
      (node (ref "X1") (pin "12") (pinfunction "12_12") (pintype "passive"))
    )
    (net (code "19") (name "Net-(2F-KL)") (class "Default")
      (node (ref "2") (pin "3") (pinfunction "KL_3") (pintype "passive"))
      (node (ref "D12") (pin "2") (pinfunction "-_2") (pintype "passive"))
      (node (ref "LED2") (pin "K") (pinfunction "C_K") (pintype "passive"))
      (node (ref "TP17") (pin "TP") (pinfunction "PP_TP") (pintype "input"))
      (node (ref "X1") (pin "11") (pinfunction "11_11") (pintype "passive"))
    )
    (net (code "20") (name "Net-(2G-KL)") (class "Default")
      (node (ref "2") (pin "4") (pinfunction "KL_4") (pintype "passive"))
      (node (ref "D2") (pin "2") (pinfunction "-_2") (pintype "passive"))
      (node (ref "LED3") (pin "K") (pinfunction "C_K") (pintype "passive"))
      (node (ref "TP18") (pin "TP") (pinfunction "PP_TP") (pintype "input"))
      (node (ref "X1") (pin "10") (pinfunction "10_10") (pintype "passive"))
    )
    (net (code "21") (name "Net-(2H-KL)") (class "Default")
      (node (ref "2") (pin "5") (pinfunction "KL_5") (pintype "passive"))
      (node (ref "D1") (pin "2") (pinfunction "-_2") (pintype "passive"))
      (node (ref "LED4") (pin "K") (pinfunction "C_K") (pintype "passive"))
      (node (ref "TP19") (pin "TP") (pinfunction "PP_TP") (pintype "input"))
      (node (ref "X1") (pin "9") (pinfunction "9_9") (pintype "passive"))
    )
    (net (code "22") (name "Net-(2I-KL)") (class "Default")
      (node (ref "2") (pin "6") (pinfunction "KL_6") (pintype "passive"))
      (node (ref "TP21") (pin "TP") (pinfunction "PP_TP") (pintype "input"))
      (node (ref "U$2") (pin "2") (pinfunction "2_2") (pintype "passive"))
    )
    (net (code "23") (name "Net-(2J-KL)") (class "Default")
      (node (ref "2") (pin "7") (pinfunction "KL_7") (pintype "passive"))
      (node (ref "LED6") (pin "A") (pinfunction "A_A") (pintype "passive"))
      (node (ref "TP22") (pin "TP") (pinfunction "PP_TP") (pintype "input"))
      (node (ref "X1") (pin "8") (pinfunction "8_8") (pintype "passive"))
    )
    (net (code "24") (name "Net-(2K-KL)") (class "Default")
      (node (ref "2") (pin "8") (pinfunction "KL_8") (pintype "passive"))
      (node (ref "D14") (pin "2") (pinfunction "-_2") (pintype "passive"))
      (node (ref "LED7") (pin "K") (pinfunction "C_K") (pintype "passive"))
      (node (ref "TP23") (pin "TP") (pinfunction "PP_TP") (pintype "input"))
      (node (ref "X1") (pin "14") (pinfunction "14_14") (pintype "passive"))
    )
    (net (code "25") (name "Net-(2L-KL)") (class "Default")
      (node (ref "2") (pin "9") (pinfunction "KL_9") (pintype "passive"))
      (node (ref "D12") (pin "1") (pinfunction "+_1") (pintype "passive"))
      (node (ref "D2") (pin "1") (pinfunction "+_1") (pintype "passive"))
      (node (ref "JP2") (pin "1") (pinfunction "1_1") (pintype "passive"))
      (node (ref "JP4") (pin "2") (pinfunction "2_2") (pintype "passive"))
      (node (ref "TP24") (pin "TP") (pinfunction "PP_TP") (pintype "input"))
    )
    (net (code "26") (name "Net-(C2-Pad1)") (class "Default")
      (node (ref "C2") (pin "1") (pinfunction "1_1") (pintype "passive"))
      (node (ref "R10") (pin "1") (pinfunction "1_1") (pintype "passive"))
      (node (ref "R12") (pin "2") (pinfunction "2_2") (pintype "passive"))
    )
    (net (code "27") (name "Net-(C11-Pad1)") (class "Default")
      (node (ref "C11") (pin "1") (pinfunction "1_1") (pintype "passive"))
      (node (ref "R42") (pin "1") (pinfunction "1_1") (pintype "passive"))
      (node (ref "R43") (pin "1") (pinfunction "1_1") (pintype "passive"))
    )
    (net (code "28") (name "Net-(D1-+)") (class "Default")
      (node (ref "D1") (pin "1") (pinfunction "+_1") (pintype "passive"))
      (node (ref "R27") (pin "1") (pinfunction "1_1") (pintype "passive"))
    )
    (net (code "29") (name "Net-(D3-+)") (class "Default")
      (node (ref "D3") (pin "1") (pinfunction "+_1") (pintype "passive"))
      (node (ref "R33") (pin "1") (pinfunction "1_1") (pintype "passive"))
    )
    (net (code "30") (name "Net-(D3--)") (class "Default")
      (node (ref "C1") (pin "2") (pinfunction "2_2") (pintype "passive"))
      (node (ref "D3") (pin "2") (pinfunction "-_2") (pintype "passive"))
      (node (ref "IC5") (pin "2") (pinfunction "TR_2") (pintype "input"))
      (node (ref "IC5") (pin "6") (pinfunction "THR_6") (pintype "input"))
      (node (ref "R24") (pin "1") (pinfunction "1_1") (pintype "passive"))
      (node (ref "U$3") (pin "6") (pinfunction "D2_6") (pintype "passive"))
    )
    (net (code "31") (name "Net-(D5-PadC)") (class "Default")
      (node (ref "D5") (pin "C") (pinfunction "C_C") (pintype "passive"))
      (node (ref "R1") (pin "2") (pinfunction "2_2") (pintype "passive"))
      (node (ref "X1") (pin "22") (pinfunction "22_22") (pintype "passive"))
    )
    (net (code "32") (name "Net-(D8-+)") (class "Default")
      (node (ref "D8") (pin "1") (pinfunction "+_1") (pintype "passive"))
      (node (ref "R17") (pin "1") (pinfunction "1_1") (pintype "passive"))
    )
    (net (code "33") (name "Net-(D8--)") (class "Default")
      (node (ref "D8") (pin "2") (pinfunction "-_2") (pintype "passive"))
      (node (ref "IC7") (pin "2") (pinfunction "OUT_2") (pintype "open_collector"))
      (node (ref "Q10") (pin "1") (pinfunction "G_1") (pintype "passive"))
      (node (ref "R22") (pin "2") (pinfunction "2_2") (pintype "passive"))
      (node (ref "U$2") (pin "1") (pinfunction "1_1") (pintype "passive"))
    )
    (net (code "34") (name "Net-(D13-+)") (class "Default")
      (node (ref "D13") (pin "1") (pinfunction "+_1") (pintype "passive"))
      (node (ref "JP2") (pin "2") (pinfunction "2_2") (pintype "passive"))
    )
    (net (code "35") (name "Net-(D14-+)") (class "Default")
      (node (ref "D14") (pin "1") (pinfunction "+_1") (pintype "passive"))
      (node (ref "JP4") (pin "1") (pinfunction "1_1") (pintype "passive"))
    )
    (net (code "36") (name "Net-(D15--)") (class "Default")
      (node (ref "D15") (pin "2") (pinfunction "-_2") (pintype "passive"))
      (node (ref "Q1") (pin "2") (pinfunction "C_2") (pintype "passive"))
      (node (ref "Q3") (pin "2") (pinfunction "C_2") (pintype "passive"))
      (node (ref "START") (pin "TP") (pinfunction "PP_TP") (pintype "input"))
      (node (ref "X1") (pin "5") (pinfunction "5_5") (pintype "passive"))
    )
    (net (code "37") (name "Net-(IC3A-A)") (class "Default")
      (node (ref "IC3") (pin "10") (pinfunction "A_10") (pintype "input"))
      (node (ref "R31") (pin "1") (pinfunction "1_1") (pintype "passive"))
      (node (ref "U$3") (pin "1") (pinfunction "D1_1") (pintype "passive"))
      (node (ref "X1") (pin "4") (pinfunction "4_4") (pintype "passive"))
      (node (ref "X3") (pin "2") (pinfunction "S_2") (pintype "passive"))
    )
    (net (code "38") (name "Net-(IC3A-B)") (class "Default")
      (node (ref "IC3") (pin "13") (pinfunction "B_13") (pintype "input"))
      (node (ref "R30") (pin "1") (pinfunction "1_1") (pintype "passive"))
      (node (ref "U$3") (pin "4") (pinfunction "D4_4") (pintype "passive"))
      (node (ref "X1") (pin "3") (pinfunction "3_3") (pintype "passive"))
      (node (ref "X3") (pin "3") (pinfunction "S_3") (pintype "passive"))
    )
    (net (code "39") (name "Net-(IC3A-C)") (class "Default")
      (node (ref "IC3") (pin "12") (pinfunction "C_12") (pintype "input"))
      (node (ref "R29") (pin "1") (pinfunction "1_1") (pintype "passive"))
      (node (ref "U$3") (pin "3") (pinfunction "D3_3") (pintype "passive"))
      (node (ref "X1") (pin "2") (pinfunction "2_2") (pintype "passive"))
      (node (ref "X3") (pin "4") (pinfunction "S_4") (pintype "passive"))
    )
    (net (code "40") (name "Net-(IC3A-Q0)") (class "Default")
      (node (ref "IC3") (pin "3") (pinfunction "Q0_3") (pintype "output"))
      (node (ref "IC6") (pin "1") (pinfunction "I1_1") (pintype "input"))
      (node (ref "IC6") (pin "2") (pinfunction "I2_2") (pintype "input"))
      (node (ref "Q11") (pin "1") (pinfunction "G_1") (pintype "passive"))
    )
    (net (code "41") (name "Net-(IC3A-Q1)") (class "Default")
      (node (ref "IC3") (pin "14") (pinfunction "Q1_14") (pintype "output"))
      (node (ref "IC6") (pin "6") (pinfunction "I6_6") (pintype "input"))
    )
    (net (code "42") (name "Net-(IC3A-Q2)") (class "Default")
      (node (ref "IC3") (pin "2") (pinfunction "Q2_2") (pintype "output"))
      (node (ref "IC6") (pin "7") (pinfunction "I7_7") (pintype "input"))
    )
    (net (code "43") (name "Net-(IC3A-Q3)") (class "Default")
      (node (ref "IC3") (pin "15") (pinfunction "Q3_15") (pintype "output"))
      (node (ref "IC6") (pin "5") (pinfunction "I5_5") (pintype "input"))
    )
    (net (code "44") (name "Net-(IC3A-Q4)") (class "Default")
      (node (ref "IC3") (pin "1") (pinfunction "Q4_1") (pintype "output"))
      (node (ref "IC6") (pin "4") (pinfunction "I4_4") (pintype "input"))
    )
    (net (code "45") (name "Net-(IC3A-Q5)") (class "Default")
      (node (ref "IC3") (pin "6") (pinfunction "Q5_6") (pintype "output"))
      (node (ref "IC6") (pin "3") (pinfunction "I3_3") (pintype "input"))
    )
    (net (code "46") (name "Net-(IC4-ADJ)") (class "Default")
      (node (ref "IC4") (pin "1") (pinfunction "ADJ_1") (pintype "input"))
      (node (ref "R18") (pin "1") (pinfunction "1_1") (pintype "passive"))
      (node (ref "R5") (pin "2") (pinfunction "2_2") (pintype "passive"))
      (node (ref "X1") (pin "7") (pinfunction "7_7") (pintype "passive"))
    )
    (net (code "47") (name "Net-(IC4-VI)") (class "Default")
      (node (ref "IC4") (pin "3") (pinfunction "VI_3") (pintype "input"))
      (node (ref "Q2") (pin "2") (pinfunction "C_2") (pintype "passive"))
      (node (ref "Q4") (pin "2") (pinfunction "C_2") (pintype "passive"))
    )
    (net (code "48") (name "Net-(IC4-VO)") (class "Default")
      (node (ref "IC4") (pin "2") (pinfunction "VO_2") (pintype "passive"))
      (node (ref "R18") (pin "2") (pinfunction "2_2") (pintype "passive"))
    )
    (net (code "49") (name "Net-(IC5-CV)") (class "Default")
      (node (ref "IC5") (pin "5") (pinfunction "CV_5") (pintype "input"))
      (node (ref "R26") (pin "2") (pinfunction "2_2") (pintype "passive"))
    )
    (net (code "50") (name "Net-(IC5-Q)") (class "Default")
      (node (ref "IC5") (pin "3") (pinfunction "Q_3") (pintype "output"))
      (node (ref "IC8") (pin "12") (pinfunction "A_12") (pintype "input"))
      (node (ref "R26") (pin "1") (pinfunction "1_1") (pintype "passive"))
    )
    (net (code "51") (name "Net-(IC6-O1)") (class "Default")
      (node (ref "IC6") (pin "16") (pinfunction "O1_16") (pintype "open_collector"))
      (node (ref "Q9") (pin "2") (pinfunction "C_2") (pintype "passive"))
      (node (ref "R3") (pin "2") (pinfunction "2_2") (pintype "passive"))
      (node (ref "T3") (pin "C") (pinfunction "C_C") (pintype "passive"))
      (node (ref "X1") (pin "21") (pinfunction "21_21") (pintype "passive"))
    )
    (net (code "52") (name "Net-(IC6-O2)") (class "Default")
      (node (ref "IC6") (pin "15") (pinfunction "O2_15") (pintype "open_collector"))
      (node (ref "R13") (pin "1") (pinfunction "1_1") (pintype "passive"))
    )
    (net (code "53") (name "Net-(IC7A-+IN)") (class "Default")
      (node (ref "IC7") (pin "5") (pinfunction "+IN_5") (pintype "input"))
      (node (ref "R15") (pin "1") (pinfunction "1_1") (pintype "passive"))
      (node (ref "R16") (pin "2") (pinfunction "2_2") (pintype "passive"))
      (node (ref "R17") (pin "2") (pinfunction "2_2") (pintype "passive"))
    )
    (net (code "54") (name "Net-(IC7A--IN)") (class "Default")
      (node (ref "C3") (pin "1") (pinfunction "1_1") (pintype "passive"))
      (node (ref "IC7") (pin "4") (pinfunction "-IN_4") (pintype "input"))
      (node (ref "R12") (pin "1") (pinfunction "1_1") (pintype "passive"))
    )
    (net (code "55") (name "Net-(IC7B-+IN)") (class "Default")
      (node (ref "IC7") (pin "7") (pinfunction "+IN_7") (pintype "input"))
      (node (ref "R25") (pin "1") (pinfunction "1_1") (pintype "passive"))
      (node (ref "R6") (pin "1") (pinfunction "1_1") (pintype "passive"))
    )
    (net (code "56") (name "Net-(IC7B--IN)") (class "Default")
      (node (ref "IC7") (pin "6") (pinfunction "-IN_6") (pintype "input"))
      (node (ref "IC7") (pin "8") (pinfunction "-IN_8") (pintype "input"))
      (node (ref "R5") (pin "1") (pinfunction "1_1") (pintype "passive"))
    )
    (net (code "57") (name "Net-(IC7B-OUT)") (class "Default")
      (node (ref "IC7") (pin "1") (pinfunction "OUT_1") (pintype "open_collector"))
      (node (ref "R10") (pin "2") (pinfunction "2_2") (pintype "passive"))
      (node (ref "R19") (pin "2") (pinfunction "2_2") (pintype "passive"))
    )
    (net (code "58") (name "Net-(IC7C-+IN)") (class "Default")
      (node (ref "C5") (pin "1") (pinfunction "1_1") (pintype "passive"))
      (node (ref "IC7") (pin "9") (pinfunction "+IN_9") (pintype "input"))
      (node (ref "R25") (pin "2") (pinfunction "2_2") (pintype "passive"))
      (node (ref "R8") (pin "2") (pinfunction "2_2") (pintype "passive"))
    )
    (net (code "59") (name "Net-(IC7C-OUT)") (class "Default")
      (node (ref "C9") (pin "2") (pinfunction "2_2") (pintype "passive"))
      (node (ref "IC7") (pin "14") (pinfunction "OUT_14") (pintype "open_collector"))
      (node (ref "R9") (pin "2") (pinfunction "2_2") (pintype "passive"))
    )
    (net (code "60") (name "Net-(IC8B-B)") (class "Default")
      (node (ref "IC8") (pin "11") (pinfunction "B_11") (pintype "input"))
      (node (ref "IC8") (pin "9") (pinfunction "~{Q}_9") (pintype "output"))
      (node (ref "R35") (pin "2") (pinfunction "2_2") (pintype "passive"))
    )
    (net (code "61") (name "Net-(IC8B-T2)") (class "Default")
      (node (ref "C10") (pin "1") (pinfunction "1_1") (pintype "passive"))
      (node (ref "IC8") (pin "14") (pinfunction "T2_14") (pintype "input"))
      (node (ref "R34") (pin "1") (pinfunction "1_1") (pintype "passive"))
    )
    (net (code "62") (name "Net-(IC10A-+IN)") (class "Default")
      (node (ref "C8") (pin "1") (pinfunction "1_1") (pintype "passive"))
      (node (ref "IC10") (pin "3") (pinfunction "+IN_3") (pintype "input"))
      (node (ref "R1") (pin "1") (pinfunction "1_1") (pintype "passive"))
    )
    (net (code "63") (name "Net-(IC10A--IN)") (class "Default")
      (node (ref "IC10") (pin "2") (pinfunction "-IN_2") (pintype "input"))
      (node (ref "R2") (pin "2") (pinfunction "2_2") (pintype "passive"))
    )
    (net (code "64") (name "Net-(IC10A-OUT)") (class "Default")
      (node (ref "IC10") (pin "1") (pinfunction "OUT_1") (pintype "output"))
      (node (ref "R42") (pin "2") (pinfunction "2_2") (pintype "passive"))
    )
    (net (code "65") (name "Net-(IC10B-+IN)") (class "Default")
      (node (ref "IC10") (pin "5") (pinfunction "+IN_5") (pintype "input"))
      (node (ref "R43") (pin "2") (pinfunction "2_2") (pintype "passive"))
      (node (ref "R44") (pin "2") (pinfunction "2_2") (pintype "passive"))
    )
    (net (code "66") (name "Net-(IC10B--IN)") (class "Default")
      (node (ref "IC10") (pin "6") (pinfunction "-IN_6") (pintype "input"))
      (node (ref "R45") (pin "1") (pinfunction "1_1") (pintype "passive"))
      (node (ref "R46") (pin "2") (pinfunction "2_2") (pintype "passive"))
    )
    (net (code "67") (name "Net-(IC10B-OUT)") (class "Default")
      (node (ref "IC10") (pin "7") (pinfunction "OUT_7") (pintype "output"))
      (node (ref "R32") (pin "1") (pinfunction "1_1") (pintype "passive"))
      (node (ref "R44") (pin "1") (pinfunction "1_1") (pintype "passive"))
    )
    (net (code "68") (name "Net-(JP1-Pad2)") (class "Default")
      (node (ref "JP1") (pin "2") (pinfunction "2_2") (pintype "passive"))
      (node (ref "R36") (pin "2") (pinfunction "2_2") (pintype "passive"))
      (node (ref "R37") (pin "2") (pinfunction "2_2") (pintype "passive"))
      (node (ref "SJ1") (pin "2") (pinfunction "2_2") (pintype "passive"))
    )
    (net (code "69") (name "Net-(JP3-Pad1)") (class "Default")
      (node (ref "JP3") (pin "1") (pinfunction "1_1") (pintype "passive"))
      (node (ref "R23") (pin "2") (pinfunction "2_2") (pintype "passive"))
    )
    (net (code "70") (name "Net-(LED1-PadA)") (class "Default")
      (node (ref "LED1") (pin "A") (pinfunction "A_A") (pintype "passive"))
      (node (ref "LED2") (pin "A") (pinfunction "A_A") (pintype "passive"))
      (node (ref "LED3") (pin "A") (pinfunction "A_A") (pintype "passive"))
      (node (ref "LED4") (pin "A") (pinfunction "A_A") (pintype "passive"))
      (node (ref "LED7") (pin "A") (pinfunction "A_A") (pintype "passive"))
      (node (ref "R11") (pin "1") (pinfunction "1_1") (pintype "passive"))
    )
    (net (code "71") (name "Net-(LED6-C)") (class "Default")
      (node (ref "LED6") (pin "K") (pinfunction "C_K") (pintype "passive"))
      (node (ref "R4") (pin "1") (pinfunction "1_1") (pintype "passive"))
    )
    (net (code "72") (name "Net-(Q1-B)") (class "Default")
      (node (ref "Q1") (pin "1") (pinfunction "B_1") (pintype "passive"))
      (node (ref "Q3") (pin "1") (pinfunction "B_1") (pintype "passive"))
      (node (ref "R13") (pin "2") (pinfunction "2_2") (pintype "passive"))
    )
    (net (code "73") (name "Net-(Q2-B)") (class "Default")
      (node (ref "Q2") (pin "1") (pinfunction "B_1") (pintype "passive"))
      (node (ref "Q4") (pin "1") (pinfunction "B_1") (pintype "passive"))
      (node (ref "R9") (pin "1") (pinfunction "1_1") (pintype "passive"))
    )
    (net (code "74") (name "Net-(Q5-B)") (class "Default")
      (node (ref "Q5") (pin "1") (pinfunction "B_1") (pintype "passive"))
      (node (ref "Q6") (pin "1") (pinfunction "B_1") (pintype "passive"))
      (node (ref "Q6") (pin "2") (pinfunction "C_2") (pintype "passive"))
      (node (ref "Q7") (pin "1") (pinfunction "B_1") (pintype "passive"))
      (node (ref "Q7") (pin "2") (pinfunction "C_2") (pintype "passive"))
      (node (ref "Q8") (pin "1") (pinfunction "B_1") (pintype "passive"))
      (node (ref "R38") (pin "1") (pinfunction "1_1") (pintype "passive"))
      (node (ref "R39") (pin "1") (pinfunction "1_1") (pintype "passive"))
      (node (ref "T1") (pin "2") (pinfunction "B_2") (pintype "passive"))
      (node (ref "T1") (pin "4") (pinfunction "B_4") (pintype "passive"))
      (node (ref "T1") (pin "6") (pinfunction "C1_6") (pintype "passive"))
      (node (ref "X2") (pin "2") (pinfunction "S_2") (pintype "passive"))
    )
    (net (code "75") (name "Net-(Q5-E)") (class "Default")
      (node (ref "Q5") (pin "3") (pinfunction "E_3") (pintype "passive"))
      (node (ref "Q8") (pin "3") (pinfunction "E_3") (pintype "passive"))
      (node (ref "R21") (pin "2") (pinfunction "2_2") (pintype "passive"))
      (node (ref "T1") (pin "1") (pinfunction "E_1") (pintype "passive"))
    )
    (net (code "76") (name "Net-(Q6-E)") (class "Default")
      (node (ref "Q6") (pin "3") (pinfunction "E_3") (pintype "passive"))
      (node (ref "Q7") (pin "3") (pinfunction "E_3") (pintype "passive"))
      (node (ref "R20") (pin "2") (pinfunction "2_2") (pintype "passive"))
      (node (ref "T1") (pin "3") (pinfunction "E_3") (pintype "passive"))
    )
    (net (code "77") (name "Net-(Q9-B)") (class "Default")
      (node (ref "Q9") (pin "1") (pinfunction "B_1") (pintype "passive"))
      (node (ref "R32") (pin "2") (pinfunction "2_2") (pintype "passive"))
      (node (ref "T3") (pin "B") (pinfunction "B_B") (pintype "passive"))
    )
    (net (code "78") (name "Net-(Q10-D)") (class "Default")
      (node (ref "Q10") (pin "3") (pinfunction "D_3") (pintype "passive"))
      (node (ref "R7") (pin "2") (pinfunction "2_2") (pintype "passive"))
    )
    (net (code "79") (name "Net-(R14-Pad1)") (class "Default")
      (node (ref "R14") (pin "1") (pinfunction "1_1") (pintype "passive"))
      (node (ref "R7") (pin "1") (pinfunction "1_1") (pintype "passive"))
      (node (ref "U$2") (pin "3") (pinfunction "3_3") (pintype "passive"))
    )
    (net (code "80") (name "Net-(R27-Pad2)") (class "Default")
      (node (ref "R27") (pin "2") (pinfunction "2_2") (pintype "passive"))
      (node (ref "R28") (pin "1") (pinfunction "1_1") (pintype "passive"))
    )
    (net (code "81") (name "Net-(R33-Pad2)") (class "Default")
      (node (ref "R33") (pin "2") (pinfunction "2_2") (pintype "passive"))
      (node (ref "X1") (pin "16") (pinfunction "16_16") (pintype "passive"))
    )
    (net (code "82") (name "VCC") (class "Default")
      (node (ref "6V") (pin "TP") (pinfunction "PP_TP") (pintype "input"))
      (node (ref "C4") (pin "1") (pinfunction "1_1") (pintype "passive"))
      (node (ref "IC1") (pin "OUT") (pinfunction "OUT_OUT") (pintype "passive"))
      (node (ref "IC10") (pin "8") (pinfunction "V+_8") (pintype "power_in"))
      (node (ref "IC2") (pin "1") (pinfunction "OUT_1") (pintype "passive"))
      (node (ref "IC7") (pin "3") (pinfunction "V+_3") (pintype "power_in"))
      (node (ref "R11") (pin "2") (pinfunction "2_2") (pintype "passive"))
      (node (ref "R15") (pin "2") (pinfunction "2_2") (pintype "passive"))
      (node (ref "R19") (pin "1") (pinfunction "1_1") (pintype "passive"))
      (node (ref "R45") (pin "2") (pinfunction "2_2") (pintype "passive"))
      (node (ref "R6") (pin "2") (pinfunction "2_2") (pintype "passive"))
    )
    (net (code "83") (name "unconnected-(IC3A-Q6-Pad7)") (class "Default")
      (node (ref "IC3") (pin "7") (pinfunction "Q6_7") (pintype "output"))
    )
    (net (code "84") (name "unconnected-(IC3A-Q7-Pad4)") (class "Default")
      (node (ref "IC3") (pin "4") (pinfunction "Q7_4") (pintype "output"))
    )
    (net (code "85") (name "unconnected-(IC3A-Q8-Pad9)") (class "Default")
      (node (ref "IC3") (pin "9") (pinfunction "Q8_9") (pintype "output"))
    )
    (net (code "86") (name "unconnected-(IC3A-Q9-Pad5)") (class "Default")
      (node (ref "IC3") (pin "5") (pinfunction "Q9_5") (pintype "output"))
    )
    (net (code "87") (name "unconnected-(IC5-DIS-Pad7)") (class "Default")
      (node (ref "IC5") (pin "7") (pinfunction "DIS_7") (pintype "input"))
    )
    (net (code "88") (name "unconnected-(IC7D-OUT-Pad13)") (class "Default")
      (node (ref "IC7") (pin "13") (pinfunction "OUT_13") (pintype "open_collector"))
    )
    (net (code "89") (name "unconnected-(IC8A-Q-Pad6)") (class "Default")
      (node (ref "IC8") (pin "6") (pinfunction "Q_6") (pintype "output"))
    )
    (net (code "90") (name "unconnected-(IC8A-T2-Pad2)") (class "Default")
      (node (ref "IC8") (pin "2") (pinfunction "T2_2") (pintype "input"))
    )
    (net (code "91") (name "unconnected-(IC8A-~{Q}-Pad7)") (class "Default")
      (node (ref "IC8") (pin "7") (pinfunction "~{Q}_7") (pintype "output"))
    )
    (net (code "92") (name "unconnected-(IC8B-Q-Pad10)") (class "Default")
      (node (ref "IC8") (pin "10") (pinfunction "Q_10") (pintype "output"))
    )
    (net (code "93") (name "unconnected-(Q3-C{slash}-Pad4)") (class "Default")
      (node (ref "Q3") (pin "4") (pinfunction "C/_4") (pintype "passive"))
    )
    (net (code "94") (name "unconnected-(Q4-C{slash}-Pad4)") (class "Default")
      (node (ref "Q4") (pin "4") (pinfunction "C/_4") (pintype "passive"))
    )
    (net (code "95") (name "unconnected-(Q5-C{slash}-Pad4)") (class "Default")
      (node (ref "Q5") (pin "4") (pinfunction "C/_4") (pintype "passive"))
    )
    (net (code "96") (name "unconnected-(Q6-C{slash}-Pad4)") (class "Default")
      (node (ref "Q6") (pin "4") (pinfunction "C/_4") (pintype "passive"))
    )
    (net (code "97") (name "unconnected-(T1A-C-Pad5)") (class "Default")
      (node (ref "T1") (pin "5") (pinfunction "C_5") (pintype "passive"))
    )
    (net (code "98") (name "unconnected-(T1B-C-Pad7)") (class "Default")
      (node (ref "T1") (pin "7") (pinfunction "C_7") (pintype "passive"))
    )
    (net (code "99") (name "unconnected-(X1-Pad20)") (class "Default")
      (node (ref "X1") (pin "20") (pinfunction "20_20") (pintype "passive"))
    )
    (net (code "100") (name "unconnected-(X1-Pad24)") (class "Default")
      (node (ref "X1") (pin "24") (pinfunction "24_24") (pintype "passive"))
    )
  )
)
